# Power.net
KiCad netlist of a schematic drawn in Altium Designer
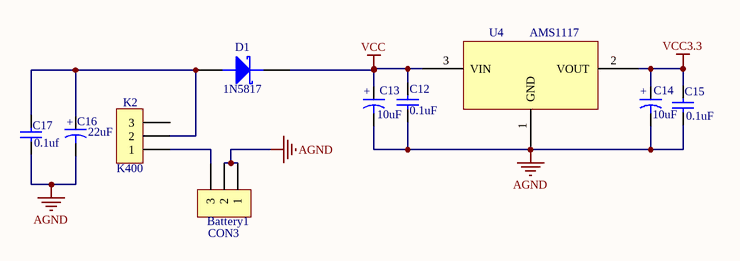
[diagram p0: Power.SchDoc]

(export (version "E")
  (design (tool "Eeschema 10.0.6"))
  (components
    (comp (ref "Battery1")
      (value "CON3")
      (footprint "J-SOURCE-micro")
      (description "Connector")
      (libsource (lib "*") (part "CON3"))
    )
    (comp (ref "C12")
      (value "0.1uF")
      (footprint "0805")
      (fields (field (name "Comment") "Capacitor-0805"))
      (libsource (lib "原理图库") (part "Capacitor-0805"))
    )
    (comp (ref "C13")
      (value "10uF")
      (footprint "钽电容1206（A3216）")
      (fields (field (name "ALTIUM_UNNAMED_1") "+") (field (name "Comment") "电解电容"))
      (libsource (lib "原理图库") (part "电解电容"))
    )
    (comp (ref "C14")
      (value "10uF")
      (footprint "钽电容1206（A3216）")
      (fields (field (name "ALTIUM_UNNAMED_1") "+") (field (name "Comment") "电解电容"))
      (libsource (lib "原理图库") (part "电解电容"))
    )
    (comp (ref "C15")
      (value "0.1uF")
      (footprint "0805")
      (fields (field (name "Comment") "Capacitor-0805"))
      (libsource (lib "原理图库") (part "Capacitor-0805"))
    )
    (comp (ref "C16")
      (value "22uF")
      (footprint "钽电容1206（A3216）")
      (fields (field (name "ALTIUM_UNNAMED_1") "+") (field (name "Comment") "电解电容"))
      (libsource (lib "集成库—大岐") (part "电解电容"))
    )
    (comp (ref "C17")
      (value "0.1uf")
      (footprint "0603")
      (fields (field (name "Comment") "Capacitor-0603"))
      (libsource (lib "原理图库") (part "Capacitor-0603"))
    )
    (comp (ref "D1")
      (value "1N5817")
      (footprint "1808")
      (description "Schottky Diode")
      (libsource (lib "*") (part "DIODE SCHOTTKY"))
    )
    (comp (ref "K2")
      (value "K400")
      (footprint "SS-12D01-edit")
      (description "Connector")
      (libsource (lib "") (part "CON3_1"))
    )
    (comp (ref "U4")
      (value "AMS1117-3.3")
      (footprint "AMS1117-3.3(SOT-23)")
      (fields (field (name "NAME") "AMS1117"))
      (libsource (lib "原理图库") (part "AMS1117-3.3"))
    )
  )
  (nets
    (net (code "1") (name "AGND") (class "Default")
      (node (ref "Battery1") (pin "1") (pinfunction "1_1") (pintype "passive"))
      (node (ref "Battery1") (pin "2") (pinfunction "2_2") (pintype "passive"))
      (node (ref "C12") (pin "1") (pinfunction "1_1") (pintype "passive"))
      (node (ref "C13") (pin "1") (pinfunction "1_1") (pintype "passive"))
      (node (ref "C14") (pin "1") (pinfunction "1_1") (pintype "passive"))
      (node (ref "C15") (pin "1") (pinfunction "1_1") (pintype "passive"))
      (node (ref "C16") (pin "1") (pinfunction "1_1") (pintype "passive"))
      (node (ref "C17") (pin "1") (pinfunction "1_1") (pintype "passive"))
      (node (ref "U4") (pin "1") (pinfunction "GND_1") (pintype "passive"))
    )
    (net (code "2") (name "Net-(Battery1-Pad3)") (class "Default")
      (node (ref "Battery1") (pin "3") (pinfunction "3_3") (pintype "passive"))
      (node (ref "K2") (pin "1") (pinfunction "1_1") (pintype "passive"))
    )
    (net (code "3") (name "Net-(D1-A)") (class "Default")
      (node (ref "C16") (pin "2") (pinfunction "2_2") (pintype "passive"))
      (node (ref "C17") (pin "2") (pinfunction "2_2") (pintype "passive"))
      (node (ref "D1") (pin "1") (pinfunction "A_1") (pintype "passive"))
      (node (ref "K2") (pin "2") (pinfunction "2_2") (pintype "passive"))
    )
    (net (code "4") (name "VCC") (class "Default")
      (node (ref "C12") (pin "2") (pinfunction "2_2") (pintype "passive"))
      (node (ref "C13") (pin "2") (pinfunction "2_2") (pintype "passive"))
      (node (ref "D1") (pin "2") (pinfunction "K_2") (pintype "passive"))
      (node (ref "U4") (pin "3") (pinfunction "VIN_3") (pintype "passive"))
    )
    (net (code "5") (name "VCC3.3") (class "Default")
      (node (ref "C14") (pin "2") (pinfunction "2_2") (pintype "passive"))
      (node (ref "C15") (pin "2") (pinfunction "2_2") (pintype "passive"))
      (node (ref "U4") (pin "2") (pinfunction "VOUT_2") (pintype "passive"))
    )
    (net (code "6") (name "unconnected-(K2-Pad3)") (class "Default")
      (node (ref "K2") (pin "3") (pinfunction "3_3") (pintype "passive"))
    )
  )
)
